# DigitalInputs.net
KiCad netlist of a schematic drawn in Altium Designer
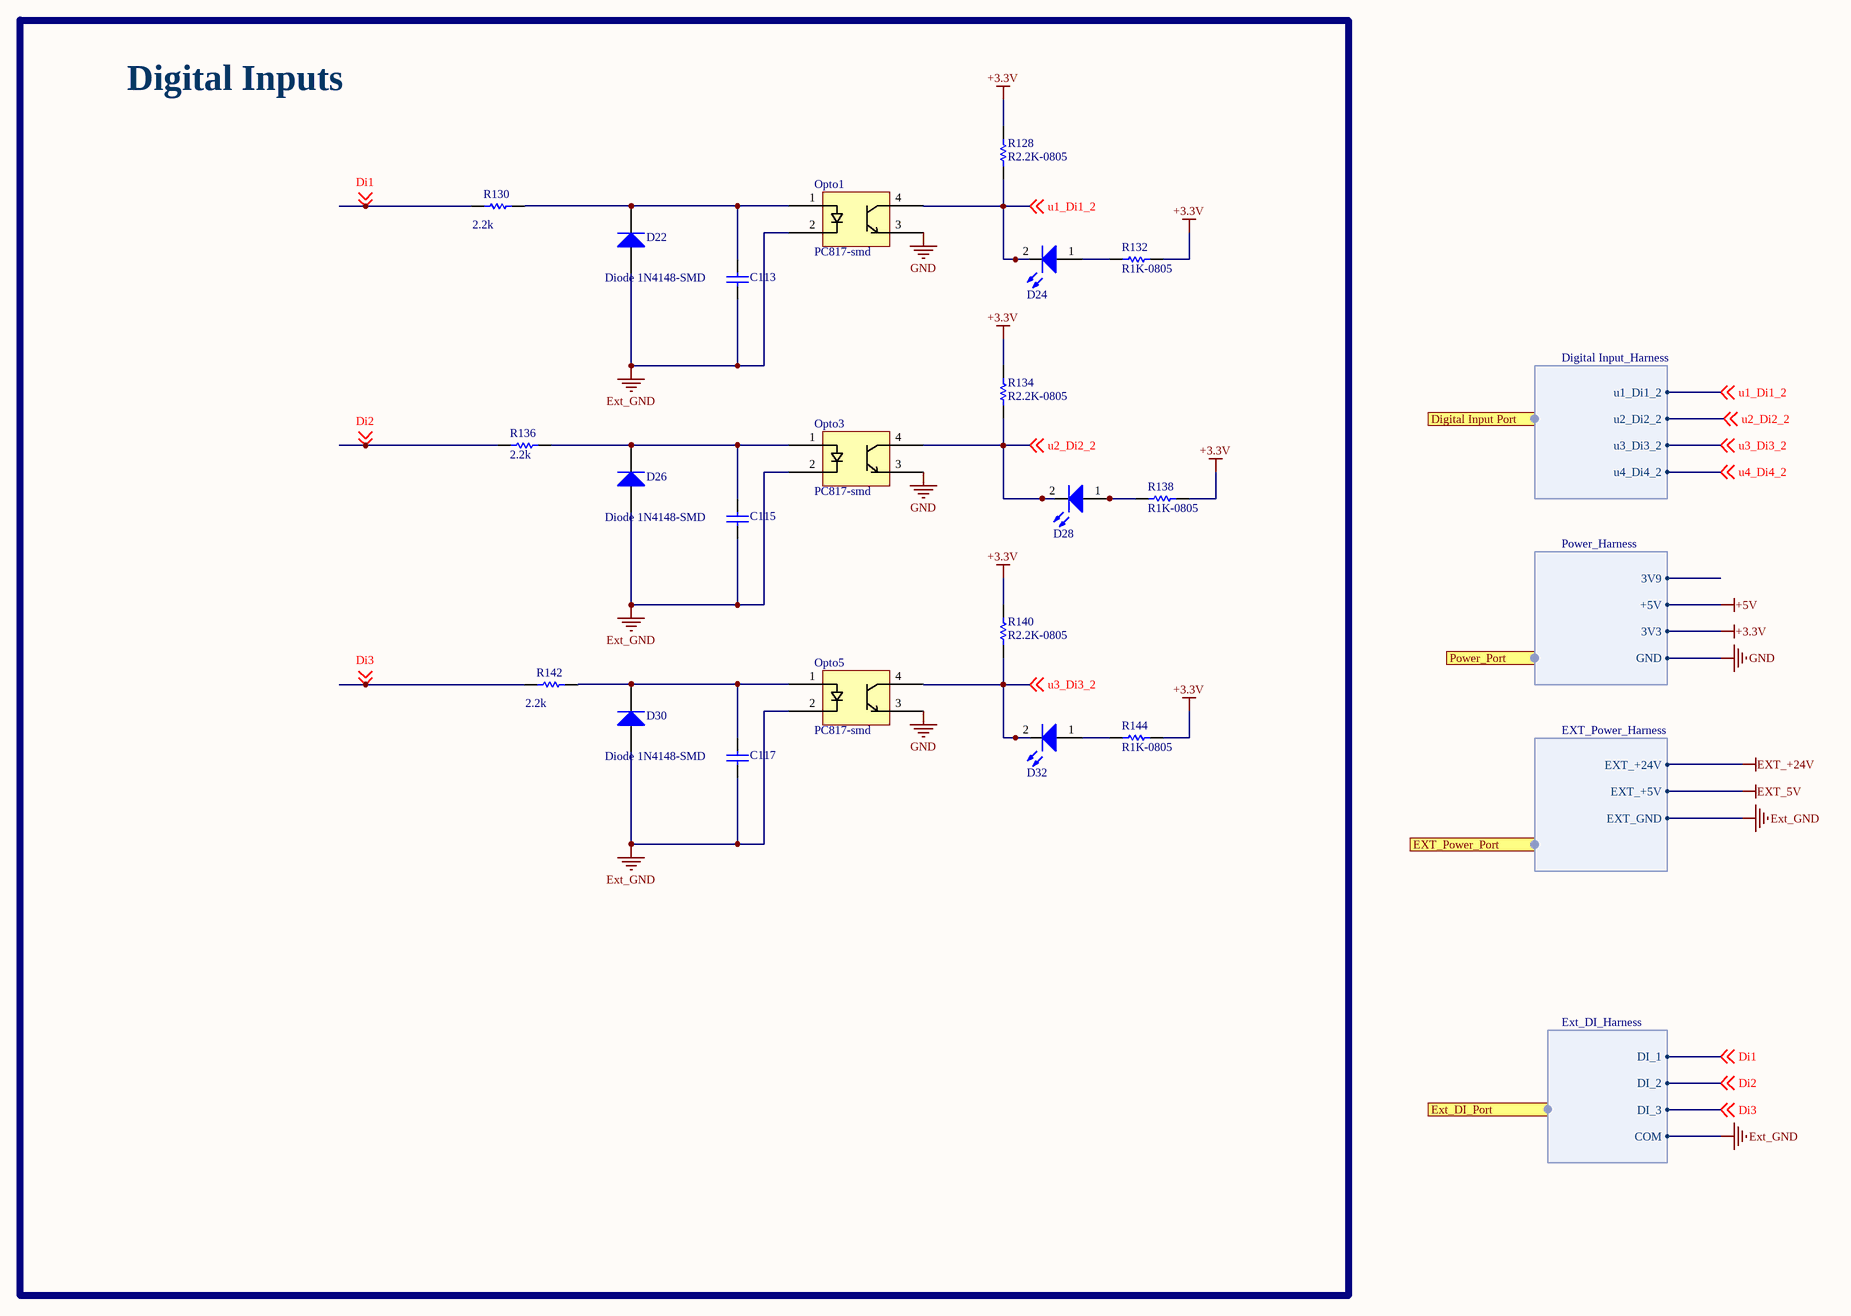
[diagram p0: DigitalInputs.SchDoc]

(export (version "E")
  (design (tool "Eeschema 10.0.6"))
  (components
    (comp (ref "C113")
      (value "~")
      (footprint "CRF06031")
      (description "Capacitor")
      (fields (field (name "DIGI-KEY_PART_NUMBER") "490-4789-1-ND"))
      (libsource (lib "Miscellaneous Devices") (part "Cap"))
    )
    (comp (ref "C115")
      (value "~")
      (footprint "CRF06031")
      (description "Capacitor")
      (fields (field (name "DIGI-KEY_PART_NUMBER") "490-4789-1-ND"))
      (libsource (lib "Miscellaneous Devices") (part "Cap"))
    )
    (comp (ref "C117")
      (value "~")
      (footprint "CRF06031")
      (description "Capacitor")
      (fields (field (name "DIGI-KEY_PART_NUMBER") "490-4789-1-ND"))
      (libsource (lib "Miscellaneous Devices") (part "Cap"))
    )
    (comp (ref "D22")
      (value "Diode 1N4148-SMD")
      (footprint "d1206")
      (description "1 Amp Fast Recovery Rectifier")
      (fields (field (name "DIGI-KEY_PART_NUMBER") "1N4148WSFSTR-ND"))
      (libsource (lib "Miscellaneous Devices") (part "Diode 1N4934"))
    )
    (comp (ref "D24")
      (value "LED_0805_green")
      (footprint "0805-LED")
      (libsource (lib "HosseinLib") (part "LED_0805"))
    )
    (comp (ref "D26")
      (value "Diode 1N4148-SMD")
      (footprint "d1206")
      (description "1 Amp Fast Recovery Rectifier")
      (fields (field (name "DIGI-KEY_PART_NUMBER") "1N4148WSFSTR-ND"))
      (libsource (lib "Miscellaneous Devices") (part "Diode 1N4934"))
    )
    (comp (ref "D28")
      (value "LED_0805_green")
      (footprint "0805-LED")
      (libsource (lib "HosseinLib") (part "LED_0805"))
    )
    (comp (ref "D30")
      (value "Diode 1N4148-SMD")
      (footprint "d1206")
      (description "1 Amp Fast Recovery Rectifier")
      (fields (field (name "DIGI-KEY_PART_NUMBER") "1N4148WSFSTR-ND"))
      (libsource (lib "Miscellaneous Devices") (part "Diode 1N4934"))
    )
    (comp (ref "D32")
      (value "LED_0805_green")
      (footprint "0805-LED")
      (libsource (lib "HosseinLib") (part "LED_0805"))
    )
    (comp (ref "Opto1")
      (value "PC817-smd")
      (footprint "PC817_SMD1")
      (fields (field (name "DIGI-KEY_PART_NUMBER") "2007-APC-817D1-SLTR-ND"))
      (libsource (lib "Almas Co") (part "PC817"))
    )
    (comp (ref "Opto3")
      (value "PC817-smd")
      (footprint "PC817_SMD1")
      (fields (field (name "DIGI-KEY_PART_NUMBER") "2007-APC-817D1-SLTR-ND"))
      (libsource (lib "Almas Co") (part "PC817"))
    )
    (comp (ref "Opto5")
      (value "PC817-smd")
      (footprint "PC817_SMD1")
      (fields (field (name "DIGI-KEY_PART_NUMBER") "2007-APC-817D1-SLTR-ND"))
      (libsource (lib "Almas Co") (part "PC817"))
    )
    (comp (ref "R128")
      (value "R2.2K-0805")
      (footprint "CRF06031")
      (description "Resistor")
      (fields (field (name "DIGI-KEY_PART_NUMBER") "311-2.20KCRTR-ND"))
      (libsource (lib "Miscellaneous Devices") (part "Res1"))
    )
    (comp (ref "R130")
      (value "2.2k")
      (footprint "r1210")
      (description "Resistor")
      (fields (field (name "DIGI-KEY_PART_NUMBER") "311-2.20KCRTR-ND"))
      (libsource (lib "Miscellaneous Devices") (part "Res1"))
    )
    (comp (ref "R132")
      (value "R1K-0805")
      (footprint "CRF06031")
      (description "Resistor")
      (fields (field (name "DIGI-KEY_PART_NUMBER") "311-1.00KCRTR-ND"))
      (libsource (lib "Miscellaneous Devices") (part "Res1"))
    )
    (comp (ref "R134")
      (value "R2.2K-0805")
      (footprint "CRF06031")
      (description "Resistor")
      (fields (field (name "DIGI-KEY_PART_NUMBER") "311-2.20KCRTR-ND"))
      (libsource (lib "Miscellaneous Devices") (part "Res1"))
    )
    (comp (ref "R136")
      (value "2.2k")
      (footprint "r1210")
      (description "Resistor")
      (fields (field (name "DIGI-KEY_PART_NUMBER") "311-2.20KCRTR-ND"))
      (libsource (lib "Miscellaneous Devices") (part "Res1"))
    )
    (comp (ref "R138")
      (value "R1K-0805")
      (footprint "CRF06031")
      (description "Resistor")
      (fields (field (name "DIGI-KEY_PART_NUMBER") "311-1.00KCRTR-ND"))
      (libsource (lib "Miscellaneous Devices") (part "Res1"))
    )
    (comp (ref "R140")
      (value "R2.2K-0805")
      (footprint "CRF06031")
      (description "Resistor")
      (fields (field (name "DIGI-KEY_PART_NUMBER") "311-2.20KCRTR-ND"))
      (libsource (lib "Miscellaneous Devices") (part "Res1"))
    )
    (comp (ref "R142")
      (value "2.2k")
      (footprint "r1210")
      (description "Resistor")
      (fields (field (name "DIGI-KEY_PART_NUMBER") "311-2.20KCRTR-ND"))
      (libsource (lib "Miscellaneous Devices") (part "Res1"))
    )
    (comp (ref "R144")
      (value "R1K-0805")
      (footprint "CRF06031")
      (description "Resistor")
      (fields (field (name "DIGI-KEY_PART_NUMBER") "311-1.00KCRTR-ND"))
      (libsource (lib "Miscellaneous Devices") (part "Res1"))
    )
  )
  (nets
    (net (code "6") (name "+3.3V") (class "Default")
      (node (ref "R128") (pin "1") (pinfunction "1_1") (pintype "passive"))
      (node (ref "R132") (pin "1") (pinfunction "1_1") (pintype "passive"))
      (node (ref "R134") (pin "1") (pinfunction "1_1") (pintype "passive"))
      (node (ref "R138") (pin "1") (pinfunction "1_1") (pintype "passive"))
      (node (ref "R140") (pin "1") (pinfunction "1_1") (pintype "passive"))
      (node (ref "R144") (pin "1") (pinfunction "1_1") (pintype "passive"))
    )
    (net (code "12") (name "Di1") (class "Default")
      (node (ref "R130") (pin "1") (pinfunction "1_1") (pintype "passive"))
    )
    (net (code "13") (name "Di2") (class "Default")
      (node (ref "R136") (pin "1") (pinfunction "1_1") (pintype "passive"))
    )
    (net (code "14") (name "Di3") (class "Default")
      (node (ref "R142") (pin "1") (pinfunction "1_1") (pintype "passive"))
    )
    (net (code "17") (name "Ext_GND") (class "Default")
      (node (ref "C113") (pin "1") (pinfunction "1_1") (pintype "passive"))
      (node (ref "C115") (pin "1") (pinfunction "1_1") (pintype "passive"))
      (node (ref "C117") (pin "1") (pinfunction "1_1") (pintype "passive"))
      (node (ref "D22") (pin "1") (pinfunction "A_1") (pintype "passive"))
      (node (ref "D26") (pin "1") (pinfunction "A_1") (pintype "passive"))
      (node (ref "D30") (pin "1") (pinfunction "A_1") (pintype "passive"))
      (node (ref "Opto1") (pin "2") (pintype "passive"))
      (node (ref "Opto3") (pin "2") (pintype "passive"))
      (node (ref "Opto5") (pin "2") (pintype "passive"))
    )
    (net (code "18") (name "GND") (class "Default")
      (node (ref "Opto1") (pin "3") (pintype "passive"))
      (node (ref "Opto3") (pin "3") (pintype "passive"))
      (node (ref "Opto5") (pin "3") (pintype "passive"))
    )
    (net (code "19") (name "Net-(D22-K)") (class "Default")
      (node (ref "C113") (pin "2") (pinfunction "2_2") (pintype "passive"))
      (node (ref "D22") (pin "2") (pinfunction "K_2") (pintype "passive"))
      (node (ref "Opto1") (pin "1") (pintype "passive"))
      (node (ref "R130") (pin "2") (pinfunction "2_2") (pintype "passive"))
    )
    (net (code "20") (name "Net-(D24-A)") (class "Default")
      (node (ref "D24") (pin "1") (pinfunction "A_1") (pintype "passive"))
      (node (ref "R132") (pin "2") (pinfunction "2_2") (pintype "passive"))
    )
    (net (code "21") (name "Net-(D26-K)") (class "Default")
      (node (ref "C115") (pin "2") (pinfunction "2_2") (pintype "passive"))
      (node (ref "D26") (pin "2") (pinfunction "K_2") (pintype "passive"))
      (node (ref "Opto3") (pin "1") (pintype "passive"))
      (node (ref "R136") (pin "2") (pinfunction "2_2") (pintype "passive"))
    )
    (net (code "22") (name "Net-(D28-A)") (class "Default")
      (node (ref "D28") (pin "1") (pinfunction "A_1") (pintype "passive"))
      (node (ref "R138") (pin "2") (pinfunction "2_2") (pintype "passive"))
    )
    (net (code "23") (name "Net-(D30-K)") (class "Default")
      (node (ref "C117") (pin "2") (pinfunction "2_2") (pintype "passive"))
      (node (ref "D30") (pin "2") (pinfunction "K_2") (pintype "passive"))
      (node (ref "Opto5") (pin "1") (pintype "passive"))
      (node (ref "R142") (pin "2") (pinfunction "2_2") (pintype "passive"))
    )
    (net (code "24") (name "Net-(D32-A)") (class "Default")
      (node (ref "D32") (pin "1") (pinfunction "A_1") (pintype "passive"))
      (node (ref "R144") (pin "2") (pinfunction "2_2") (pintype "passive"))
    )
    (net (code "25") (name "u1_Di1_2") (class "Default")
      (node (ref "D24") (pin "2") (pinfunction "K_2") (pintype "passive"))
      (node (ref "Opto1") (pin "4") (pintype "passive"))
      (node (ref "R128") (pin "2") (pinfunction "2_2") (pintype "passive"))
    )
    (net (code "26") (name "u2_Di2_2") (class "Default")
      (node (ref "D28") (pin "2") (pinfunction "K_2") (pintype "passive"))
      (node (ref "Opto3") (pin "4") (pintype "passive"))
      (node (ref "R134") (pin "2") (pinfunction "2_2") (pintype "passive"))
    )
    (net (code "27") (name "u3_Di3_2") (class "Default")
      (node (ref "D32") (pin "2") (pinfunction "K_2") (pintype "passive"))
      (node (ref "Opto5") (pin "4") (pintype "passive"))
      (node (ref "R140") (pin "2") (pinfunction "2_2") (pintype "passive"))
    )
  )
)
